# lightclock_0.net
KiCad netlist of a schematic drawn in EAGLE
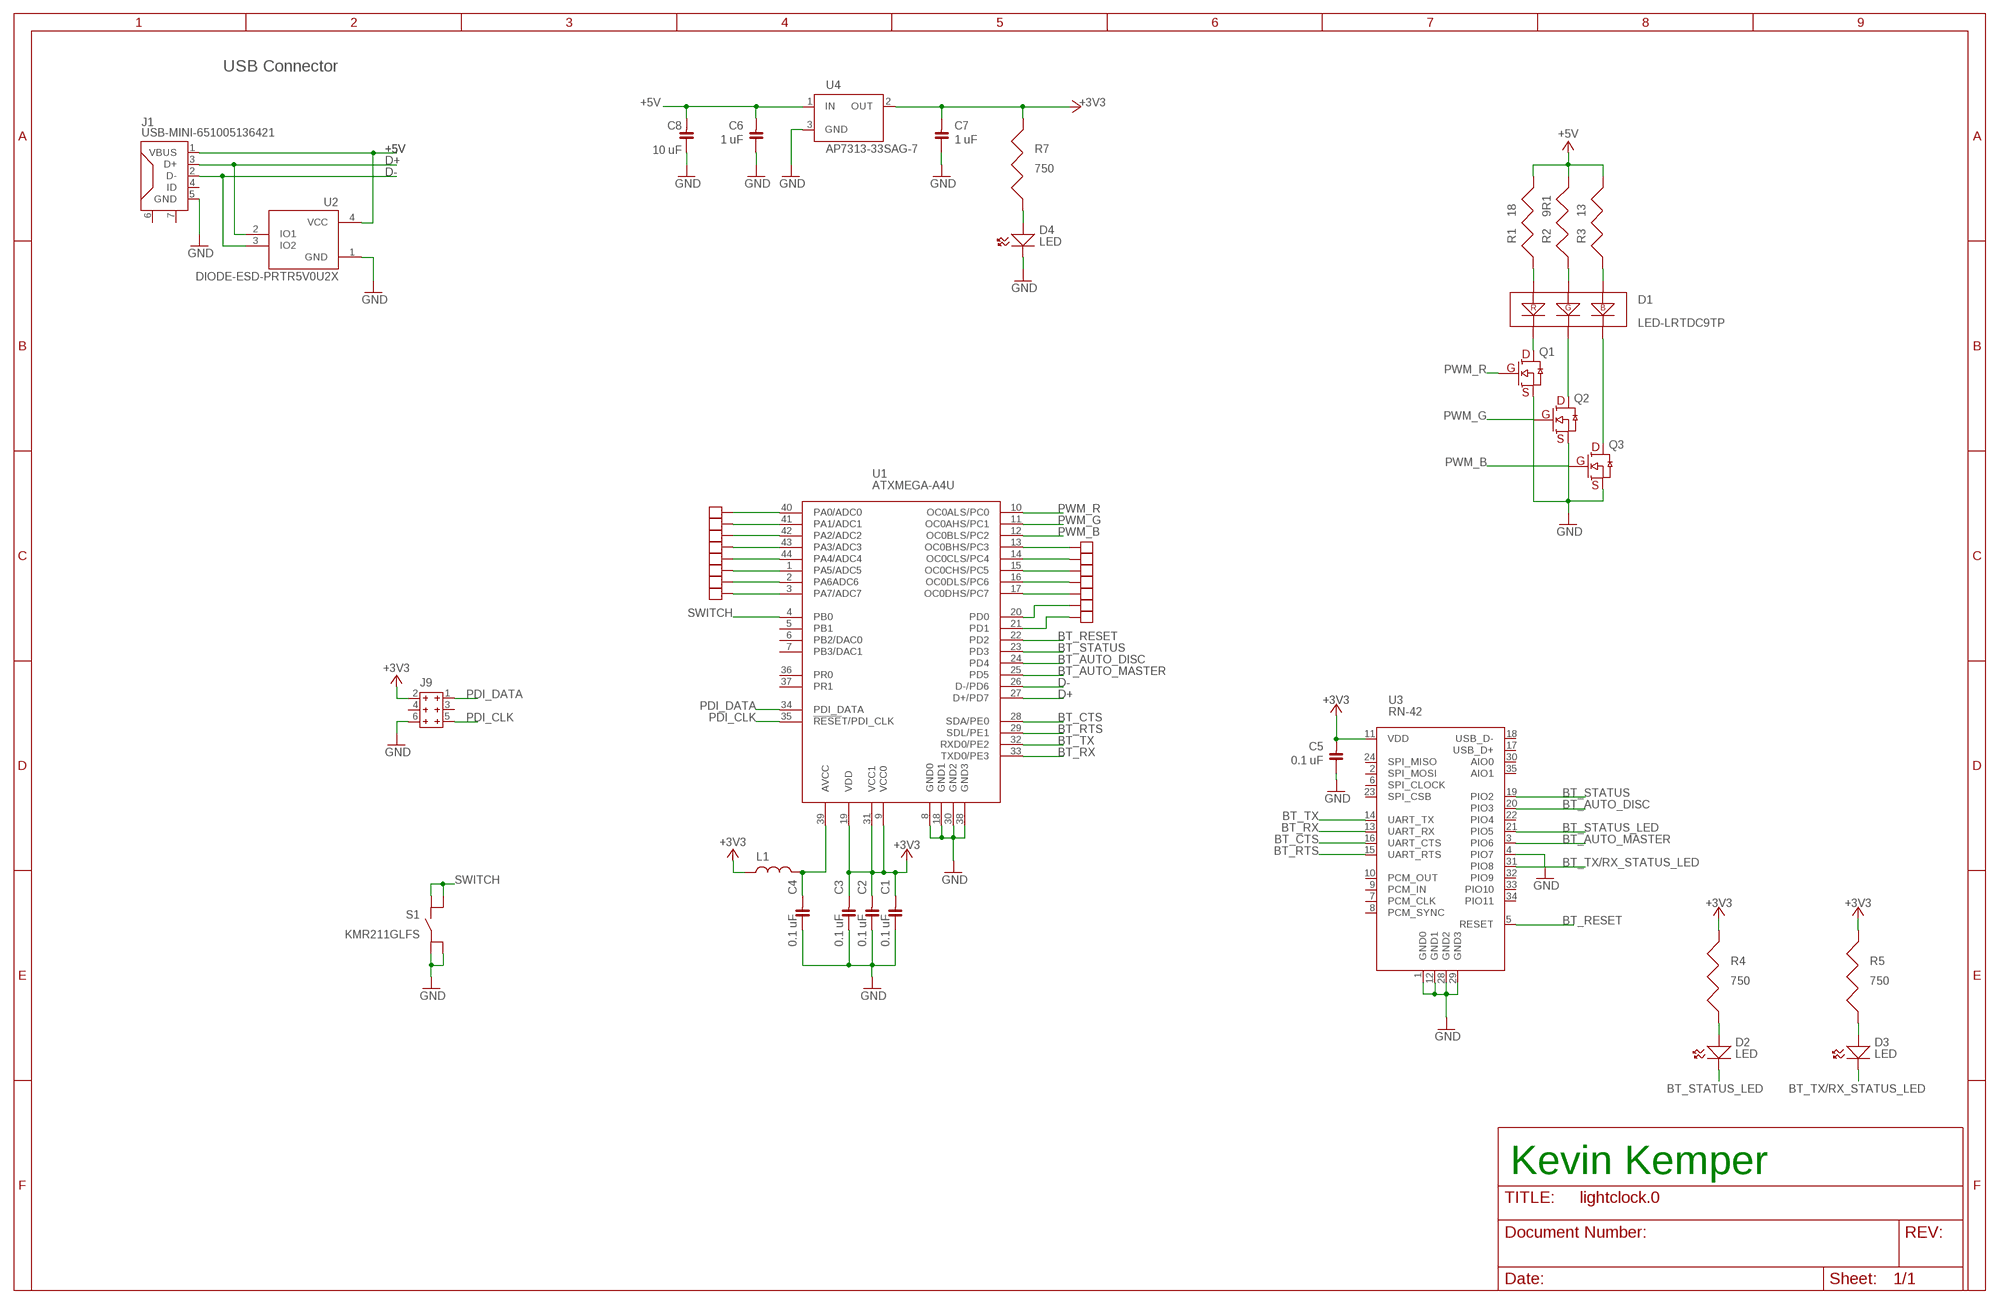
[diagram p0: schematic, sheet 1]

(export (version "E")
  (design (tool "Eeschema 10.0.6"))
  (components
    (comp (ref "C1")
      (value "0.1 uF")
      (footprint "eagle-import:0603")
      (libsource (lib "eagle-import") (part "CAP-0603"))
    )
    (comp (ref "C2")
      (value "0.1 uF")
      (footprint "eagle-import:0603")
      (libsource (lib "eagle-import") (part "CAP-0603"))
    )
    (comp (ref "C3")
      (value "0.1 uF")
      (footprint "eagle-import:0603")
      (libsource (lib "eagle-import") (part "CAP-0603"))
    )
    (comp (ref "C4")
      (value "0.1 uF")
      (footprint "eagle-import:0603")
      (libsource (lib "eagle-import") (part "CAP-0603"))
    )
    (comp (ref "C5")
      (value "0.1 uF")
      (footprint "eagle-import:0603")
      (libsource (lib "eagle-import") (part "CAP-0603"))
    )
    (comp (ref "C6")
      (value "1 uF")
      (footprint "eagle-import:0603")
      (libsource (lib "eagle-import") (part "CAP-0603"))
    )
    (comp (ref "C7")
      (value "1 uF")
      (footprint "eagle-import:0603")
      (libsource (lib "eagle-import") (part "CAP-0603"))
    )
    (comp (ref "C8")
      (value "10 uF")
      (footprint "eagle-import:0805")
      (libsource (lib "eagle-import") (part "CAP-0805"))
    )
    (comp (ref "D1")
      (value "LED-LRTDC9TP")
      (footprint "eagle-import:LRTDC9TP-EAFB-GHQN")
      (libsource (lib "eagle-import") (part "LED-LRTDC9TP"))
    )
    (comp (ref "D2")
      (value "LED")
      (footprint "eagle-import:0603-POL")
      (libsource (lib "eagle-import") (part "LED"))
    )
    (comp (ref "D3")
      (value "LED")
      (footprint "eagle-import:0603-POL")
      (libsource (lib "eagle-import") (part "LED"))
    )
    (comp (ref "D4")
      (value "LED")
      (footprint "eagle-import:0603-POL")
      (libsource (lib "eagle-import") (part "LED"))
    )
    (comp (ref "J1")
      (value "USB-MINI-651005136421")
      (footprint "eagle-import:651005136421")
      (libsource (lib "eagle-import") (part "USB-MINI-651005136421"))
    )
    (comp (ref "J2")
      (value "TESTPAD")
      (footprint "eagle-import:HEADER-1X1")
      (libsource (lib "eagle-import") (part "TESTPAD"))
    )
    (comp (ref "J3")
      (value "TESTPAD")
      (footprint "eagle-import:HEADER-1X1")
      (libsource (lib "eagle-import") (part "TESTPAD"))
    )
    (comp (ref "J4")
      (value "TESTPAD")
      (footprint "eagle-import:HEADER-1X1")
      (libsource (lib "eagle-import") (part "TESTPAD"))
    )
    (comp (ref "J5")
      (value "TESTPAD")
      (footprint "eagle-import:HEADER-1X1")
      (libsource (lib "eagle-import") (part "TESTPAD"))
    )
    (comp (ref "J6")
      (value "TESTPAD")
      (footprint "eagle-import:HEADER-1X1")
      (libsource (lib "eagle-import") (part "TESTPAD"))
    )
    (comp (ref "J7")
      (value "TESTPAD")
      (footprint "eagle-import:HEADER-1X1")
      (libsource (lib "eagle-import") (part "TESTPAD"))
    )
    (comp (ref "J8")
      (value "TESTPAD")
      (footprint "eagle-import:HEADER-1X1")
      (libsource (lib "eagle-import") (part "TESTPAD"))
    )
    (comp (ref "J9")
      (value "HEADER-2X6")
      (footprint "eagle-import:HEADER-2X6")
      (libsource (lib "eagle-import") (part "HEADER-2X6"))
    )
    (comp (ref "J10")
      (value "TESTPAD")
      (footprint "eagle-import:HEADER-1X1")
      (libsource (lib "eagle-import") (part "TESTPAD"))
    )
    (comp (ref "J11")
      (value "TESTPAD")
      (footprint "eagle-import:HEADER-1X1")
      (libsource (lib "eagle-import") (part "TESTPAD"))
    )
    (comp (ref "J12")
      (value "TESTPAD")
      (footprint "eagle-import:HEADER-1X1")
      (libsource (lib "eagle-import") (part "TESTPAD"))
    )
    (comp (ref "J13")
      (value "TESTPAD")
      (footprint "eagle-import:HEADER-1X1")
      (libsource (lib "eagle-import") (part "TESTPAD"))
    )
    (comp (ref "J14")
      (value "TESTPAD")
      (footprint "eagle-import:HEADER-1X1")
      (libsource (lib "eagle-import") (part "TESTPAD"))
    )
    (comp (ref "J15")
      (value "TESTPAD")
      (footprint "eagle-import:HEADER-1X1")
      (libsource (lib "eagle-import") (part "TESTPAD"))
    )
    (comp (ref "J16")
      (value "TESTPAD")
      (footprint "eagle-import:HEADER-1X1")
      (libsource (lib "eagle-import") (part "TESTPAD"))
    )
    (comp (ref "J17")
      (value "TESTPAD")
      (footprint "eagle-import:HEADER-1X1")
      (libsource (lib "eagle-import") (part "TESTPAD"))
    )
    (comp (ref "L1")
      (value "IND-0603")
      (footprint "eagle-import:0603")
      (libsource (lib "eagle-import") (part "IND-0603"))
    )
    (comp (ref "Q1")
      (value "BSS138")
      (footprint "eagle-import:SOT-23")
      (libsource (lib "eagle-import") (part "BSS138"))
    )
    (comp (ref "Q2")
      (value "BSS138")
      (footprint "eagle-import:SOT-23")
      (libsource (lib "eagle-import") (part "BSS138"))
    )
    (comp (ref "Q3")
      (value "BSS138")
      (footprint "eagle-import:SOT-23")
      (libsource (lib "eagle-import") (part "BSS138"))
    )
    (comp (ref "R1")
      (value "18")
      (footprint "eagle-import:2010")
      (libsource (lib "eagle-import") (part "RES2010"))
    )
    (comp (ref "R2")
      (value "9R1")
      (footprint "eagle-import:2010")
      (libsource (lib "eagle-import") (part "RES2010"))
    )
    (comp (ref "R3")
      (value "13")
      (footprint "eagle-import:2010")
      (libsource (lib "eagle-import") (part "RES2010"))
    )
    (comp (ref "R4")
      (value "750")
      (footprint "eagle-import:0603")
      (libsource (lib "eagle-import") (part "RES-0603"))
    )
    (comp (ref "R5")
      (value "750")
      (footprint "eagle-import:0603")
      (libsource (lib "eagle-import") (part "RES-0603"))
    )
    (comp (ref "R7")
      (value "750")
      (footprint "eagle-import:0603")
      (libsource (lib "eagle-import") (part "RES-0603"))
    )
    (comp (ref "S1")
      (value "KMR211GLFS")
      (footprint "eagle-import:KMR211GLFS")
      (libsource (lib "eagle-import") (part "KMR211GLFS"))
    )
    (comp (ref "U1")
      (value "ATXMEGA-A4U")
      (footprint "eagle-import:ATXMEGA16A4U-AUR")
      (libsource (lib "eagle-import") (part "ATXMEGA-A4U"))
    )
    (comp (ref "U2")
      (value "DIODE-ESD-PRTR5V0U2X")
      (footprint "eagle-import:PRTR5V0U2X")
      (libsource (lib "eagle-import") (part "DIODE-ESD-PRTR5V0U2X"))
    )
    (comp (ref "U3")
      (value "RN-42")
      (footprint "eagle-import:RN-42")
      (libsource (lib "eagle-import") (part "RN-42"))
    )
    (comp (ref "U4")
      (value "AP7313-33SAG-7")
      (footprint "eagle-import:AP7313-33SAG-7")
      (libsource (lib "eagle-import") (part "AP7313-33SAG-7"))
    )
  )
  (nets
    (net (code "1") (name "+3V3") (class "Default")
      (node (ref "C1") (pin "1") (pinfunction "1_1") (pintype "bidirectional"))
      (node (ref "C2") (pin "1") (pinfunction "1_1") (pintype "bidirectional"))
      (node (ref "C3") (pin "1") (pinfunction "1_1") (pintype "bidirectional"))
      (node (ref "C5") (pin "1") (pinfunction "1_1") (pintype "bidirectional"))
      (node (ref "C7") (pin "1") (pinfunction "1_1") (pintype "bidirectional"))
      (node (ref "J9") (pin "2") (pinfunction "2_2") (pintype "bidirectional"))
      (node (ref "L1") (pin "1") (pinfunction "P$1_1") (pintype "bidirectional"))
      (node (ref "R4") (pin "2") (pinfunction "P$2_2") (pintype "bidirectional"))
      (node (ref "R5") (pin "2") (pinfunction "P$2_2") (pintype "bidirectional"))
      (node (ref "R7") (pin "2") (pinfunction "P$2_2") (pintype "bidirectional"))
      (node (ref "U1") (pin "19") (pinfunction "VDD_19") (pintype "bidirectional"))
      (node (ref "U1") (pin "31") (pinfunction "VCC1_31") (pintype "bidirectional"))
      (node (ref "U1") (pin "9") (pinfunction "VCC0_9") (pintype "bidirectional"))
      (node (ref "U3") (pin "11") (pinfunction "VDD_11") (pintype "bidirectional"))
      (node (ref "U4") (pin "2") (pinfunction "OUT_2") (pintype "bidirectional"))
    )
    (net (code "2") (name "+5V") (class "Default")
      (node (ref "C6") (pin "1") (pinfunction "1_1") (pintype "bidirectional"))
      (node (ref "C8") (pin "1") (pinfunction "1_1") (pintype "bidirectional"))
      (node (ref "J1") (pin "1") (pinfunction "VBUS_1") (pintype "bidirectional"))
      (node (ref "R1") (pin "2") (pinfunction "P$2_2") (pintype "bidirectional"))
      (node (ref "R2") (pin "2") (pinfunction "P$2_2") (pintype "bidirectional"))
      (node (ref "R3") (pin "2") (pinfunction "P$2_2") (pintype "bidirectional"))
      (node (ref "U2") (pin "4") (pinfunction "VCC_4") (pintype "bidirectional"))
      (node (ref "U4") (pin "1") (pinfunction "IN_1") (pintype "bidirectional"))
    )
    (net (code "3") (name "/BT_AUTO_DISC") (class "Default")
      (node (ref "U1") (pin "24") (pinfunction "PD4_24") (pintype "bidirectional"))
      (node (ref "U3") (pin "20") (pinfunction "PIO3_20") (pintype "bidirectional"))
    )
    (net (code "4") (name "/BT_AUTO_MASTER") (class "Default")
      (node (ref "U1") (pin "25") (pinfunction "PD5_25") (pintype "bidirectional"))
      (node (ref "U3") (pin "3") (pinfunction "PIO6_3") (pintype "bidirectional"))
    )
    (net (code "5") (name "/BT_CTS") (class "Default")
      (node (ref "U1") (pin "28") (pinfunction "SDA/PE0_28") (pintype "bidirectional"))
      (node (ref "U3") (pin "16") (pinfunction "UART_CTS_16") (pintype "bidirectional"))
    )
    (net (code "6") (name "/BT_RESET") (class "Default")
      (node (ref "U1") (pin "22") (pinfunction "PD2_22") (pintype "bidirectional"))
      (node (ref "U3") (pin "5") (pinfunction "RESET_5") (pintype "bidirectional"))
    )
    (net (code "7") (name "/BT_RTS") (class "Default")
      (node (ref "U1") (pin "29") (pinfunction "SDL/PE1_29") (pintype "bidirectional"))
      (node (ref "U3") (pin "15") (pinfunction "UART_RTS_15") (pintype "bidirectional"))
    )
    (net (code "8") (name "/BT_RX") (class "Default")
      (node (ref "U1") (pin "33") (pinfunction "TXD0/PE3_33") (pintype "bidirectional"))
      (node (ref "U3") (pin "13") (pinfunction "UART_RX_13") (pintype "bidirectional"))
    )
    (net (code "9") (name "/BT_STATUS") (class "Default")
      (node (ref "U1") (pin "23") (pinfunction "PD3_23") (pintype "bidirectional"))
      (node (ref "U3") (pin "19") (pinfunction "PIO2_19") (pintype "bidirectional"))
    )
    (net (code "10") (name "/BT_STATUS_LED") (class "Default")
      (node (ref "D2") (pin "2") (pinfunction "2_2") (pintype "bidirectional"))
      (node (ref "U3") (pin "21") (pinfunction "PIO5_21") (pintype "bidirectional"))
    )
    (net (code "11") (name "/BT_TX") (class "Default")
      (node (ref "U1") (pin "32") (pinfunction "RXD0/PE2_32") (pintype "bidirectional"))
      (node (ref "U3") (pin "14") (pinfunction "UART_TX_14") (pintype "bidirectional"))
    )
    (net (code "12") (name "/BT_TX{slash}RX_STATUS_LED") (class "Default")
      (node (ref "D3") (pin "2") (pinfunction "2_2") (pintype "bidirectional"))
      (node (ref "U3") (pin "31") (pinfunction "PIO8_31") (pintype "bidirectional"))
    )
    (net (code "13") (name "/D+") (class "Default")
      (node (ref "J1") (pin "3") (pinfunction "D+_3") (pintype "bidirectional"))
      (node (ref "U1") (pin "27") (pinfunction "D+/PD7_27") (pintype "bidirectional"))
      (node (ref "U2") (pin "2") (pinfunction "IO1_2") (pintype "bidirectional"))
    )
    (net (code "14") (name "/D-") (class "Default")
      (node (ref "J1") (pin "2") (pinfunction "D-_2") (pintype "bidirectional"))
      (node (ref "U1") (pin "26") (pinfunction "D-/PD6_26") (pintype "bidirectional"))
      (node (ref "U2") (pin "3") (pinfunction "IO2_3") (pintype "bidirectional"))
    )
    (net (code "15") (name "/PDI_CLK") (class "Default")
      (node (ref "J9") (pin "5") (pinfunction "5_5") (pintype "bidirectional"))
      (node (ref "U1") (pin "35") (pinfunction "~{RESE}T/PDI_CLK_35") (pintype "bidirectional"))
    )
    (net (code "16") (name "/PDI_DATA") (class "Default")
      (node (ref "J9") (pin "1") (pinfunction "1_1") (pintype "bidirectional"))
      (node (ref "U1") (pin "34") (pinfunction "PDI_DATA_34") (pintype "bidirectional"))
    )
    (net (code "17") (name "/PWM_B") (class "Default")
      (node (ref "Q3") (pin "1") (pinfunction "G_1") (pintype "bidirectional"))
      (node (ref "U1") (pin "12") (pinfunction "OC0BLS/PC2_12") (pintype "bidirectional"))
    )
    (net (code "18") (name "/PWM_G") (class "Default")
      (node (ref "Q2") (pin "1") (pinfunction "G_1") (pintype "bidirectional"))
      (node (ref "U1") (pin "11") (pinfunction "OC0AHS/PC1_11") (pintype "bidirectional"))
    )
    (net (code "19") (name "/PWM_R") (class "Default")
      (node (ref "Q1") (pin "1") (pinfunction "G_1") (pintype "bidirectional"))
      (node (ref "U1") (pin "10") (pinfunction "OC0ALS/PC0_10") (pintype "bidirectional"))
    )
    (net (code "20") (name "/SWITCH") (class "Default")
      (node (ref "S1") (pin "3") (pinfunction "3_3") (pintype "bidirectional"))
      (node (ref "S1") (pin "4") (pinfunction "4_4") (pintype "bidirectional"))
      (node (ref "U1") (pin "4") (pinfunction "PB0_4") (pintype "bidirectional"))
    )
    (net (code "21") (name "GND") (class "Default")
      (node (ref "C1") (pin "2") (pinfunction "2_2") (pintype "bidirectional"))
      (node (ref "C2") (pin "2") (pinfunction "2_2") (pintype "bidirectional"))
      (node (ref "C3") (pin "2") (pinfunction "2_2") (pintype "bidirectional"))
      (node (ref "C4") (pin "2") (pinfunction "2_2") (pintype "bidirectional"))
      (node (ref "C5") (pin "2") (pinfunction "2_2") (pintype "bidirectional"))
      (node (ref "C6") (pin "2") (pinfunction "2_2") (pintype "bidirectional"))
      (node (ref "C7") (pin "2") (pinfunction "2_2") (pintype "bidirectional"))
      (node (ref "C8") (pin "2") (pinfunction "2_2") (pintype "bidirectional"))
      (node (ref "D4") (pin "2") (pinfunction "2_2") (pintype "bidirectional"))
      (node (ref "J1") (pin "5") (pinfunction "GND_5") (pintype "bidirectional"))
      (node (ref "J9") (pin "6") (pinfunction "6_6") (pintype "bidirectional"))
      (node (ref "Q1") (pin "2") (pinfunction "S_2") (pintype "bidirectional"))
      (node (ref "Q2") (pin "2") (pinfunction "S_2") (pintype "bidirectional"))
      (node (ref "Q3") (pin "2") (pinfunction "S_2") (pintype "bidirectional"))
      (node (ref "S1") (pin "1") (pinfunction "1_1") (pintype "bidirectional"))
      (node (ref "S1") (pin "2") (pinfunction "2_2") (pintype "bidirectional"))
      (node (ref "U1") (pin "18") (pinfunction "GND1_18") (pintype "bidirectional"))
      (node (ref "U1") (pin "30") (pinfunction "GND2_30") (pintype "bidirectional"))
      (node (ref "U1") (pin "38") (pinfunction "GND3_38") (pintype "bidirectional"))
      (node (ref "U1") (pin "8") (pinfunction "GND0_8") (pintype "bidirectional"))
      (node (ref "U2") (pin "1") (pinfunction "GND_1") (pintype "bidirectional"))
      (node (ref "U3") (pin "1") (pinfunction "GND0_1") (pintype "bidirectional"))
      (node (ref "U3") (pin "12") (pinfunction "GND1_12") (pintype "bidirectional"))
      (node (ref "U3") (pin "28") (pinfunction "GND2_28") (pintype "bidirectional"))
      (node (ref "U3") (pin "29") (pinfunction "GND3_29") (pintype "bidirectional"))
      (node (ref "U3") (pin "4") (pinfunction "PIO7_4") (pintype "bidirectional"))
      (node (ref "U4") (pin "3") (pinfunction "GND_3") (pintype "bidirectional"))
    )
    (net (code "22") (name "Net-(J2-P$1)") (class "Default")
      (node (ref "J2") (pin "1") (pinfunction "P$1_1") (pintype "bidirectional"))
      (node (ref "U1") (pin "13") (pinfunction "OC0BHS/PC3_13") (pintype "bidirectional"))
    )
    (net (code "23") (name "Net-(J3-P$1)") (class "Default")
      (node (ref "J3") (pin "1") (pinfunction "P$1_1") (pintype "bidirectional"))
      (node (ref "U1") (pin "14") (pinfunction "OC0CLS/PC4_14") (pintype "bidirectional"))
    )
    (net (code "24") (name "Net-(J4-P$1)") (class "Default")
      (node (ref "J4") (pin "1") (pinfunction "P$1_1") (pintype "bidirectional"))
      (node (ref "U1") (pin "15") (pinfunction "OC0CHS/PC5_15") (pintype "bidirectional"))
    )
    (net (code "25") (name "Net-(J5-P$1)") (class "Default")
      (node (ref "J5") (pin "1") (pinfunction "P$1_1") (pintype "bidirectional"))
      (node (ref "U1") (pin "16") (pinfunction "OC0DLS/PC6_16") (pintype "bidirectional"))
    )
    (net (code "26") (name "Net-(J6-P$1)") (class "Default")
      (node (ref "J6") (pin "1") (pinfunction "P$1_1") (pintype "bidirectional"))
      (node (ref "U1") (pin "17") (pinfunction "OC0DHS/PC7_17") (pintype "bidirectional"))
    )
    (net (code "27") (name "Net-(J7-P$1)") (class "Default")
      (node (ref "J7") (pin "1") (pinfunction "P$1_1") (pintype "bidirectional"))
      (node (ref "U1") (pin "20") (pinfunction "PD0_20") (pintype "bidirectional"))
    )
    (net (code "28") (name "Net-(J8-P$1)") (class "Default")
      (node (ref "J8") (pin "1") (pinfunction "P$1_1") (pintype "bidirectional"))
      (node (ref "U1") (pin "21") (pinfunction "PD1_21") (pintype "bidirectional"))
    )
    (net (code "29") (name "Net-(J10-P$1)") (class "Default")
      (node (ref "J10") (pin "1") (pinfunction "P$1_1") (pintype "bidirectional"))
      (node (ref "U1") (pin "40") (pinfunction "PA0/ADC0_40") (pintype "bidirectional"))
    )
    (net (code "30") (name "Net-(J11-P$1)") (class "Default")
      (node (ref "J11") (pin "1") (pinfunction "P$1_1") (pintype "bidirectional"))
      (node (ref "U1") (pin "41") (pinfunction "PA1/ADC1_41") (pintype "bidirectional"))
    )
    (net (code "31") (name "Net-(J12-P$1)") (class "Default")
      (node (ref "J12") (pin "1") (pinfunction "P$1_1") (pintype "bidirectional"))
      (node (ref "U1") (pin "42") (pinfunction "PA2/ADC2_42") (pintype "bidirectional"))
    )
    (net (code "32") (name "Net-(J13-P$1)") (class "Default")
      (node (ref "J13") (pin "1") (pinfunction "P$1_1") (pintype "bidirectional"))
      (node (ref "U1") (pin "43") (pinfunction "PA3/ADC3_43") (pintype "bidirectional"))
    )
    (net (code "33") (name "Net-(J14-P$1)") (class "Default")
      (node (ref "J14") (pin "1") (pinfunction "P$1_1") (pintype "bidirectional"))
      (node (ref "U1") (pin "44") (pinfunction "PA4/ADC4_44") (pintype "bidirectional"))
    )
    (net (code "34") (name "Net-(J15-P$1)") (class "Default")
      (node (ref "J15") (pin "1") (pinfunction "P$1_1") (pintype "bidirectional"))
      (node (ref "U1") (pin "1") (pinfunction "PA5/ADC5_1") (pintype "bidirectional"))
    )
    (net (code "35") (name "Net-(J16-P$1)") (class "Default")
      (node (ref "J16") (pin "1") (pinfunction "P$1_1") (pintype "bidirectional"))
      (node (ref "U1") (pin "2") (pinfunction "PA6ADC6_2") (pintype "bidirectional"))
    )
    (net (code "36") (name "Net-(J17-P$1)") (class "Default")
      (node (ref "J17") (pin "1") (pinfunction "P$1_1") (pintype "bidirectional"))
      (node (ref "U1") (pin "3") (pinfunction "PA7/ADC7_3") (pintype "bidirectional"))
    )
    (net (code "37") (name "Net-(L1-P$2)") (class "Default")
      (node (ref "C4") (pin "1") (pinfunction "1_1") (pintype "bidirectional"))
      (node (ref "L1") (pin "2") (pinfunction "P$2_2") (pintype "bidirectional"))
      (node (ref "U1") (pin "39") (pinfunction "AVCC_39") (pintype "bidirectional"))
    )
    (net (code "38") (name "Net-(Q1-D)") (class "Default")
      (node (ref "D1") (pin "C1") (pinfunction "C1_C1") (pintype "bidirectional"))
      (node (ref "Q1") (pin "3") (pinfunction "D_3") (pintype "bidirectional"))
    )
    (net (code "39") (name "Net-(Q2-D)") (class "Default")
      (node (ref "D1") (pin "C2") (pinfunction "C2_C2") (pintype "bidirectional"))
      (node (ref "Q2") (pin "3") (pinfunction "D_3") (pintype "bidirectional"))
    )
    (net (code "40") (name "Net-(Q3-D)") (class "Default")
      (node (ref "D1") (pin "C3") (pinfunction "C3_C3") (pintype "bidirectional"))
      (node (ref "Q3") (pin "3") (pinfunction "D_3") (pintype "bidirectional"))
    )
    (net (code "41") (name "Net-(R1-P$1)") (class "Default")
      (node (ref "D1") (pin "A1") (pinfunction "A1_A1") (pintype "bidirectional"))
      (node (ref "R1") (pin "1") (pinfunction "P$1_1") (pintype "bidirectional"))
    )
    (net (code "42") (name "Net-(R2-P$1)") (class "Default")
      (node (ref "D1") (pin "A2") (pinfunction "A2_A2") (pintype "bidirectional"))
      (node (ref "R2") (pin "1") (pinfunction "P$1_1") (pintype "bidirectional"))
    )
    (net (code "43") (name "Net-(R3-P$1)") (class "Default")
      (node (ref "D1") (pin "A3") (pinfunction "A3_A3") (pintype "bidirectional"))
      (node (ref "R3") (pin "1") (pinfunction "P$1_1") (pintype "bidirectional"))
    )
    (net (code "44") (name "Net-(R4-P$1)") (class "Default")
      (node (ref "D2") (pin "1") (pinfunction "1_1") (pintype "bidirectional"))
      (node (ref "R4") (pin "1") (pinfunction "P$1_1") (pintype "bidirectional"))
    )
    (net (code "45") (name "Net-(R5-P$1)") (class "Default")
      (node (ref "D3") (pin "1") (pinfunction "1_1") (pintype "bidirectional"))
      (node (ref "R5") (pin "1") (pinfunction "P$1_1") (pintype "bidirectional"))
    )
    (net (code "46") (name "Net-(R7-P$1)") (class "Default")
      (node (ref "D4") (pin "1") (pinfunction "1_1") (pintype "bidirectional"))
      (node (ref "R7") (pin "1") (pinfunction "P$1_1") (pintype "bidirectional"))
    )
    (net (code "47") (name "unconnected-(J1-ID-Pad4)") (class "Default")
      (node (ref "J1") (pin "4") (pinfunction "ID_4") (pintype "bidirectional"))
    )
    (net (code "48") (name "unconnected-(J1-SHEILD1-Pad6)") (class "Default")
      (node (ref "J1") (pin "6") (pinfunction "SHEILD1_6") (pintype "bidirectional"))
    )
    (net (code "49") (name "unconnected-(J1-SHEILD2-Pad7)") (class "Default")
      (node (ref "J1") (pin "7") (pinfunction "SHEILD2_7") (pintype "bidirectional"))
    )
    (net (code "50") (name "unconnected-(J9-Pad3)") (class "Default")
      (node (ref "J9") (pin "3") (pinfunction "3_3") (pintype "bidirectional"))
    )
    (net (code "51") (name "unconnected-(J9-Pad4)") (class "Default")
      (node (ref "J9") (pin "4") (pinfunction "4_4") (pintype "bidirectional"))
    )
    (net (code "52") (name "unconnected-(U1-PB1-Pad5)") (class "Default")
      (node (ref "U1") (pin "5") (pinfunction "PB1_5") (pintype "bidirectional"))
    )
    (net (code "53") (name "unconnected-(U1-PB2{slash}DAC0-Pad6)") (class "Default")
      (node (ref "U1") (pin "6") (pinfunction "PB2/DAC0_6") (pintype "bidirectional"))
    )
    (net (code "54") (name "unconnected-(U1-PB3{slash}DAC1-Pad7)") (class "Default")
      (node (ref "U1") (pin "7") (pinfunction "PB3/DAC1_7") (pintype "bidirectional"))
    )
    (net (code "55") (name "unconnected-(U1-PR0-Pad36)") (class "Default")
      (node (ref "U1") (pin "36") (pinfunction "PR0_36") (pintype "bidirectional"))
    )
    (net (code "56") (name "unconnected-(U1-PR1-Pad37)") (class "Default")
      (node (ref "U1") (pin "37") (pinfunction "PR1_37") (pintype "bidirectional"))
    )
    (net (code "57") (name "unconnected-(U3-AIO0-Pad30)") (class "Default")
      (node (ref "U3") (pin "30") (pinfunction "AIO0_30") (pintype "bidirectional"))
    )
    (net (code "58") (name "unconnected-(U3-AIO1-Pad35)") (class "Default")
      (node (ref "U3") (pin "35") (pinfunction "AIO1_35") (pintype "bidirectional"))
    )
    (net (code "59") (name "unconnected-(U3-PCM_CLK-Pad7)") (class "Default")
      (node (ref "U3") (pin "7") (pinfunction "PCM_CLK_7") (pintype "bidirectional"))
    )
    (net (code "60") (name "unconnected-(U3-PCM_IN-Pad9)") (class "Default")
      (node (ref "U3") (pin "9") (pinfunction "PCM_IN_9") (pintype "bidirectional"))
    )
    (net (code "61") (name "unconnected-(U3-PCM_OUT-Pad10)") (class "Default")
      (node (ref "U3") (pin "10") (pinfunction "PCM_OUT_10") (pintype "bidirectional"))
    )
    (net (code "62") (name "unconnected-(U3-PCM_SYNC-Pad8)") (class "Default")
      (node (ref "U3") (pin "8") (pinfunction "PCM_SYNC_8") (pintype "bidirectional"))
    )
    (net (code "63") (name "unconnected-(U3-PIO4-Pad22)") (class "Default")
      (node (ref "U3") (pin "22") (pinfunction "PIO4_22") (pintype "bidirectional"))
    )
    (net (code "64") (name "unconnected-(U3-PIO9-Pad32)") (class "Default")
      (node (ref "U3") (pin "32") (pinfunction "PIO9_32") (pintype "bidirectional"))
    )
    (net (code "65") (name "unconnected-(U3-PIO10-Pad33)") (class "Default")
      (node (ref "U3") (pin "33") (pinfunction "PIO10_33") (pintype "bidirectional"))
    )
    (net (code "66") (name "unconnected-(U3-PIO11-Pad34)") (class "Default")
      (node (ref "U3") (pin "34") (pinfunction "PIO11_34") (pintype "bidirectional"))
    )
    (net (code "67") (name "unconnected-(U3-SPI_CLOCK-Pad6)") (class "Default")
      (node (ref "U3") (pin "6") (pinfunction "SPI_CLOCK_6") (pintype "bidirectional"))
    )
    (net (code "68") (name "unconnected-(U3-SPI_CSB-Pad23)") (class "Default")
      (node (ref "U3") (pin "23") (pinfunction "SPI_CSB_23") (pintype "bidirectional"))
    )
    (net (code "69") (name "unconnected-(U3-SPI_MISO-Pad24)") (class "Default")
      (node (ref "U3") (pin "24") (pinfunction "SPI_MISO_24") (pintype "bidirectional"))
    )
    (net (code "70") (name "unconnected-(U3-SPI_MOSI-Pad2)") (class "Default")
      (node (ref "U3") (pin "2") (pinfunction "SPI_MOSI_2") (pintype "bidirectional"))
    )
    (net (code "71") (name "unconnected-(U3-USB_D+-Pad17)") (class "Default")
      (node (ref "U3") (pin "17") (pinfunction "USB_D+_17") (pintype "bidirectional"))
    )
    (net (code "72") (name "unconnected-(U3-USB_D--Pad18)") (class "Default")
      (node (ref "U3") (pin "18") (pinfunction "USB_D-_18") (pintype "bidirectional"))
    )
  )
)
